# 1A18J2_1A20J2_A.net
KiCad netlist of a schematic drawn in Altium Designer
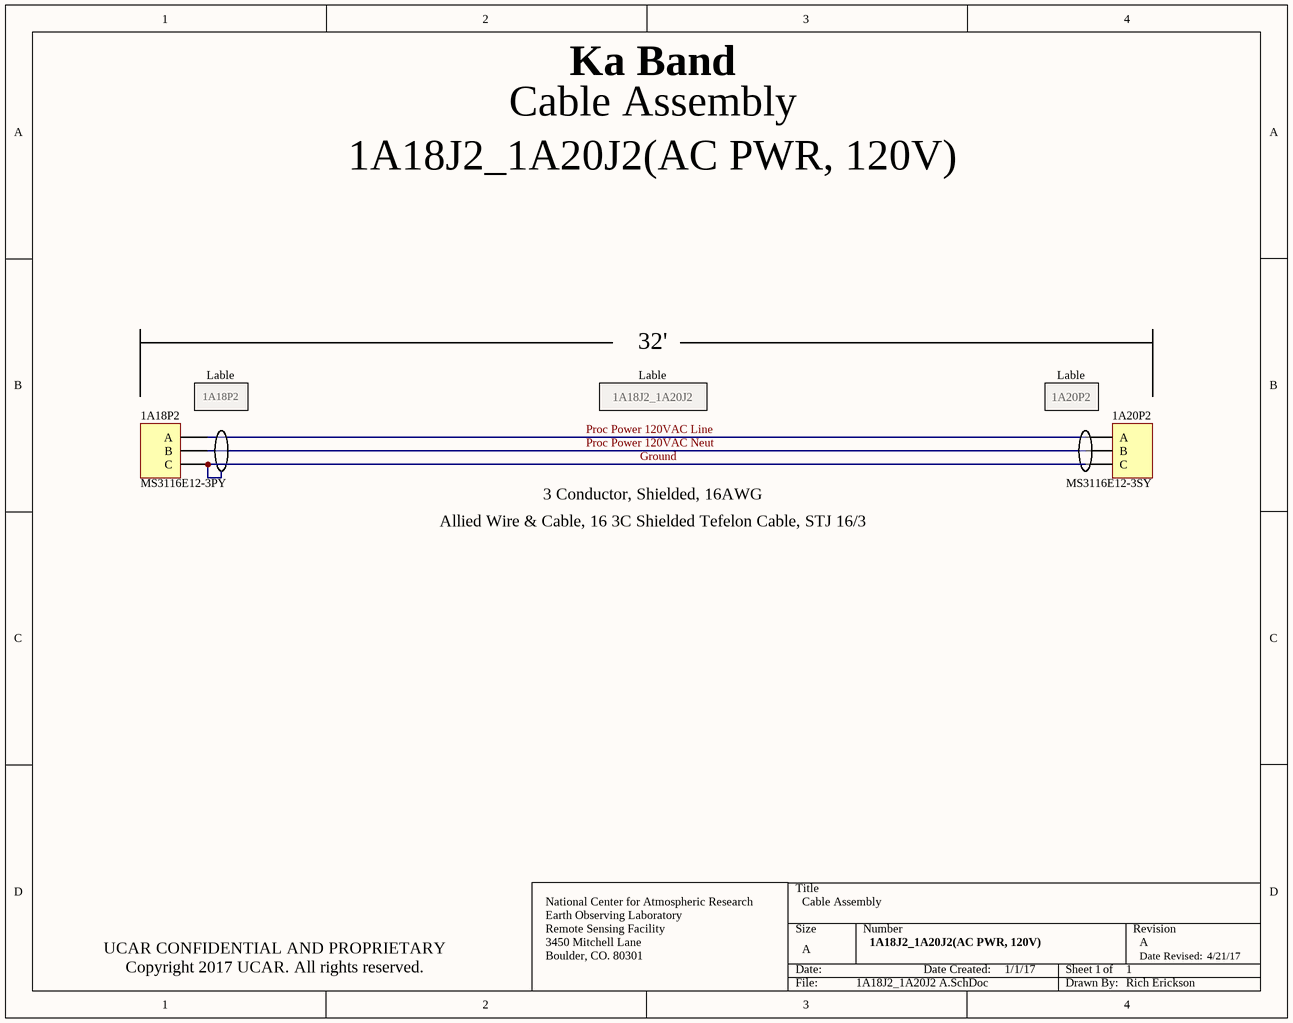
[diagram p0: 1A18J2_1A20J2 A.SchDoc]

(export (version "E")
  (design (tool "Eeschema 10.0.6"))
  (components
    (comp (ref "1A18P2")
      (value "MS3116E12-3PY")
      (footprint "HDR1X3")
      (description "Header, 3-Pin")
      (fields (field (name "PUBLISHER") "Altium Limited"))
      (libsource (lib "Miscellaneous Connectors") (part "Header 3"))
    )
    (comp (ref "1A20P2")
      (value "MS3116E12-3SY")
      (footprint "HDR1X3")
      (description "Header, 3-Pin")
      (fields (field (name "PUBLISHER") "Altium Limited"))
      (libsource (lib "") (part "Header 3_1"))
    )
  )
  (nets
    (net (code "1") (name "/Ground") (class "Default")
      (node (ref "1A18P2") (pin "3") (pinfunction "C_3") (pintype "passive"))
      (node (ref "1A20P2") (pin "3") (pinfunction "C_3") (pintype "passive"))
    )
    (net (code "2") (name "/Proc Power 120VAC Line") (class "Default")
      (node (ref "1A18P2") (pin "1") (pinfunction "A_1") (pintype "passive"))
      (node (ref "1A20P2") (pin "1") (pinfunction "A_1") (pintype "passive"))
    )
    (net (code "3") (name "/Proc Power 120VAC Neut") (class "Default")
      (node (ref "1A18P2") (pin "2") (pinfunction "B_2") (pintype "passive"))
      (node (ref "1A20P2") (pin "2") (pinfunction "B_2") (pintype "passive"))
    )
  )
)
